# tweeq-eMod_Splitter_I2C.net
KiCad netlist of a schematic drawn in EAGLE
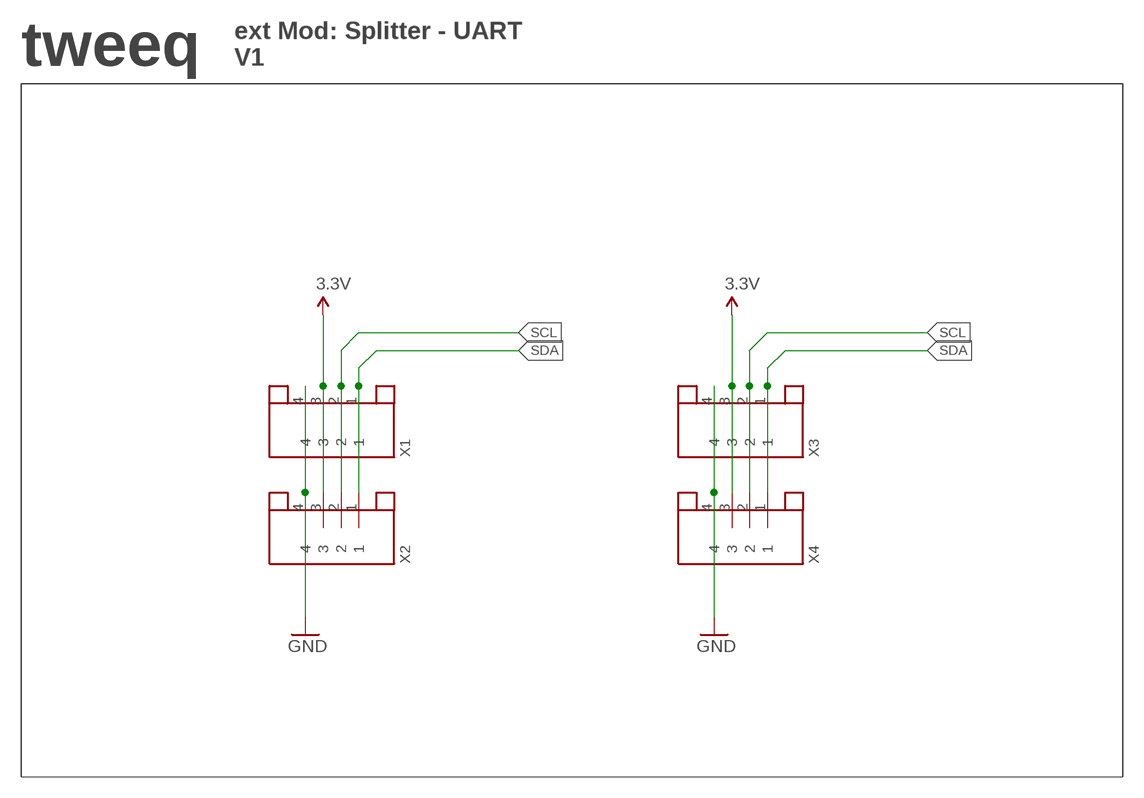
[diagram p0: schematic, sheet 1]

(export (version "E")
  (design (tool "Eeschema 10.0.6"))
  (components
    (comp (ref "X1")
      (value "JST-4PINSH")
      (footprint "eagle-import:SH1.0-4PIN")
      (libsource (lib "eagle-import") (part "JST-4PINSH"))
    )
    (comp (ref "X2")
      (value "JST-4PINSH")
      (footprint "eagle-import:SH1.0-4PIN")
      (libsource (lib "eagle-import") (part "JST-4PINSH"))
    )
    (comp (ref "X3")
      (value "JST-4PINSH")
      (footprint "eagle-import:SH1.0-4PIN")
      (libsource (lib "eagle-import") (part "JST-4PINSH"))
    )
    (comp (ref "X4")
      (value "JST-4PINSH")
      (footprint "eagle-import:SH1.0-4PIN")
      (libsource (lib "eagle-import") (part "JST-4PINSH"))
    )
  )
  (nets
    (net (code "1") (name "3.3V") (class "Default")
      (node (ref "X1") (pin "3") (pinfunction "3_3") (pintype "bidirectional"))
      (node (ref "X2") (pin "3") (pinfunction "3_3") (pintype "bidirectional"))
      (node (ref "X3") (pin "3") (pinfunction "3_3") (pintype "bidirectional"))
      (node (ref "X4") (pin "3") (pinfunction "3_3") (pintype "bidirectional"))
    )
    (net (code "2") (name "GND") (class "Default")
      (node (ref "X1") (pin "4") (pinfunction "4_4") (pintype "bidirectional"))
      (node (ref "X2") (pin "4") (pinfunction "4_4") (pintype "bidirectional"))
      (node (ref "X3") (pin "4") (pinfunction "4_4") (pintype "bidirectional"))
      (node (ref "X4") (pin "4") (pinfunction "4_4") (pintype "bidirectional"))
    )
    (net (code "3") (name "SCL") (class "Default")
      (node (ref "X1") (pin "2") (pinfunction "2_2") (pintype "bidirectional"))
      (node (ref "X2") (pin "2") (pinfunction "2_2") (pintype "bidirectional"))
      (node (ref "X3") (pin "2") (pinfunction "2_2") (pintype "bidirectional"))
      (node (ref "X4") (pin "2") (pinfunction "2_2") (pintype "bidirectional"))
    )
    (net (code "4") (name "SDA") (class "Default")
      (node (ref "X1") (pin "1") (pinfunction "1_1") (pintype "bidirectional"))
      (node (ref "X2") (pin "1") (pinfunction "1_1") (pintype "bidirectional"))
      (node (ref "X3") (pin "1") (pinfunction "1_1") (pintype "bidirectional"))
      (node (ref "X4") (pin "1") (pinfunction "1_1") (pintype "bidirectional"))
    )
  )
)
